# RFID_UNIT.net
KiCad netlist of a schematic drawn in EAGLE
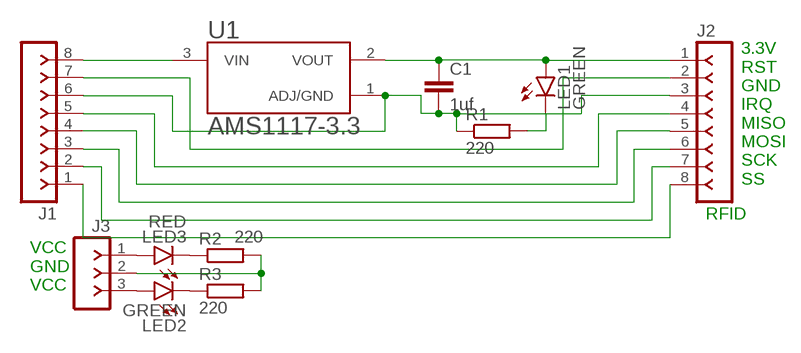
[diagram p0: schematic, sheet 1]

(export (version "E")
  (design (tool "Eeschema 10.0.6"))
  (components
    (comp (ref "C1")
      (value "1uf")
      (footprint "eagle-import:C025-025X050")
      (libsource (lib "eagle-import") (part "C-EU025-025X050"))
    )
    (comp (ref "J1")
      (value "F-1X08-SIP-100-32Y")
      (footprint "eagle-import:SIP-100-08-32Y")
      (libsource (lib "eagle-import") (part "F-1X08-SIP-100-32Y"))
    )
    (comp (ref "J2")
      (value "F-1X08-SIP-100-32Y")
      (footprint "eagle-import:SIP-100-08-32Y")
      (libsource (lib "eagle-import") (part "F-1X08-SIP-100-32Y"))
    )
    (comp (ref "J3")
      (value "F-1X03-SIP-100-32Y")
      (footprint "eagle-import:SIP-100-03-32Y")
      (libsource (lib "eagle-import") (part "F-1X03-SIP-100-32Y"))
    )
    (comp (ref "LED1")
      (value "GREEN")
      (footprint "eagle-import:SML0805")
      (libsource (lib "eagle-import") (part "LEDSML0805"))
    )
    (comp (ref "LED2")
      (value "GREEN")
      (footprint "eagle-import:LED5MM")
      (libsource (lib "eagle-import") (part "LED5MM"))
    )
    (comp (ref "LED3")
      (value "RED")
      (footprint "eagle-import:LED5MM")
      (libsource (lib "eagle-import") (part "LED5MM"))
    )
    (comp (ref "R1")
      (value "220")
      (footprint "eagle-import:0204_7")
      (libsource (lib "eagle-import") (part "R-EU_0204/7"))
    )
    (comp (ref "R2")
      (value "220")
      (footprint "eagle-import:0204_7")
      (libsource (lib "eagle-import") (part "R-EU_0204/7"))
    )
    (comp (ref "R3")
      (value "220")
      (footprint "eagle-import:0204_7")
      (libsource (lib "eagle-import") (part "R-EU_0204/7"))
    )
    (comp (ref "U1")
      (value "AMS1117-3.3")
      (footprint "eagle-import:SOT229P700X180-4N")
      (fields (field (name "MF") "Advanced Monolithic Systems"))
      (libsource (lib "eagle-import") (part "AMS1117-3.3"))
    )
  )
  (nets
    (net (code "1") (name "Net-(J1-Pad1)") (class "Default")
      (node (ref "J1") (pin "1") (pinfunction "1_1") (pintype "passive"))
      (node (ref "J2") (pin "8") (pinfunction "8_8") (pintype "passive"))
    )
    (net (code "2") (name "Net-(J1-Pad2)") (class "Default")
      (node (ref "J1") (pin "2") (pinfunction "2_2") (pintype "passive"))
      (node (ref "J2") (pin "7") (pinfunction "7_7") (pintype "passive"))
    )
    (net (code "3") (name "Net-(J1-Pad3)") (class "Default")
      (node (ref "J1") (pin "3") (pinfunction "3_3") (pintype "passive"))
      (node (ref "J2") (pin "6") (pinfunction "6_6") (pintype "passive"))
    )
    (net (code "4") (name "Net-(J1-Pad4)") (class "Default")
      (node (ref "J1") (pin "4") (pinfunction "4_4") (pintype "passive"))
      (node (ref "J2") (pin "5") (pinfunction "5_5") (pintype "passive"))
    )
    (net (code "5") (name "Net-(J1-Pad5)") (class "Default")
      (node (ref "J1") (pin "5") (pinfunction "5_5") (pintype "passive"))
      (node (ref "J2") (pin "4") (pinfunction "4_4") (pintype "passive"))
    )
    (net (code "6") (name "Net-(J1-Pad7)") (class "Default")
      (node (ref "J1") (pin "7") (pinfunction "7_7") (pintype "passive"))
      (node (ref "J2") (pin "2") (pinfunction "2_2") (pintype "passive"))
    )
    (net (code "7") (name "Net-(J3-Pad1)") (class "Default")
      (node (ref "J3") (pin "1") (pinfunction "1_1") (pintype "passive"))
      (node (ref "LED3") (pin "A") (pinfunction "A_A") (pintype "passive"))
    )
    (net (code "8") (name "Net-(J3-Pad2)") (class "Default")
      (node (ref "J3") (pin "2") (pinfunction "2_2") (pintype "passive"))
      (node (ref "R2") (pin "2") (pinfunction "2_2") (pintype "passive"))
      (node (ref "R3") (pin "2") (pinfunction "2_2") (pintype "passive"))
    )
    (net (code "9") (name "Net-(J3-Pad3)") (class "Default")
      (node (ref "J3") (pin "3") (pinfunction "3_3") (pintype "passive"))
      (node (ref "LED2") (pin "A") (pinfunction "A_A") (pintype "passive"))
    )
    (net (code "10") (name "Net-(LED1-PadC)") (class "Default")
      (node (ref "LED1") (pin "C") (pinfunction "C_C") (pintype "passive"))
      (node (ref "R1") (pin "2") (pinfunction "2_2") (pintype "passive"))
    )
    (net (code "11") (name "Net-(LED2-C)") (class "Default")
      (node (ref "LED2") (pin "K") (pinfunction "C_K") (pintype "passive"))
      (node (ref "R3") (pin "1") (pinfunction "1_1") (pintype "passive"))
    )
    (net (code "12") (name "Net-(LED3-C)") (class "Default")
      (node (ref "LED3") (pin "K") (pinfunction "C_K") (pintype "passive"))
      (node (ref "R2") (pin "1") (pinfunction "1_1") (pintype "passive"))
    )
    (net (code "13") (name "Net-(U1-ADJ{slash}GND)") (class "Default")
      (node (ref "C1") (pin "2") (pinfunction "2_2") (pintype "passive"))
      (node (ref "J1") (pin "6") (pinfunction "6_6") (pintype "passive"))
      (node (ref "J2") (pin "3") (pinfunction "3_3") (pintype "passive"))
      (node (ref "R1") (pin "1") (pinfunction "1_1") (pintype "passive"))
      (node (ref "U1") (pin "1") (pinfunction "ADJ/GND_1") (pintype "power_in"))
    )
    (net (code "14") (name "Net-(U1-VIN)") (class "Default")
      (node (ref "J1") (pin "8") (pinfunction "8_8") (pintype "passive"))
      (node (ref "U1") (pin "3") (pinfunction "VIN_3") (pintype "input"))
    )
    (net (code "15") (name "Net-(U1-VOUT)") (class "Default")
      (node (ref "C1") (pin "1") (pinfunction "1_1") (pintype "passive"))
      (node (ref "J2") (pin "1") (pinfunction "1_1") (pintype "passive"))
      (node (ref "LED1") (pin "A") (pinfunction "A_A") (pintype "passive"))
      (node (ref "U1") (pin "2") (pinfunction "VOUT_2") (pintype "output"))
    )
  )
)
